# fpga-ground.net
KiCad netlist of a schematic drawn in Altium Designer
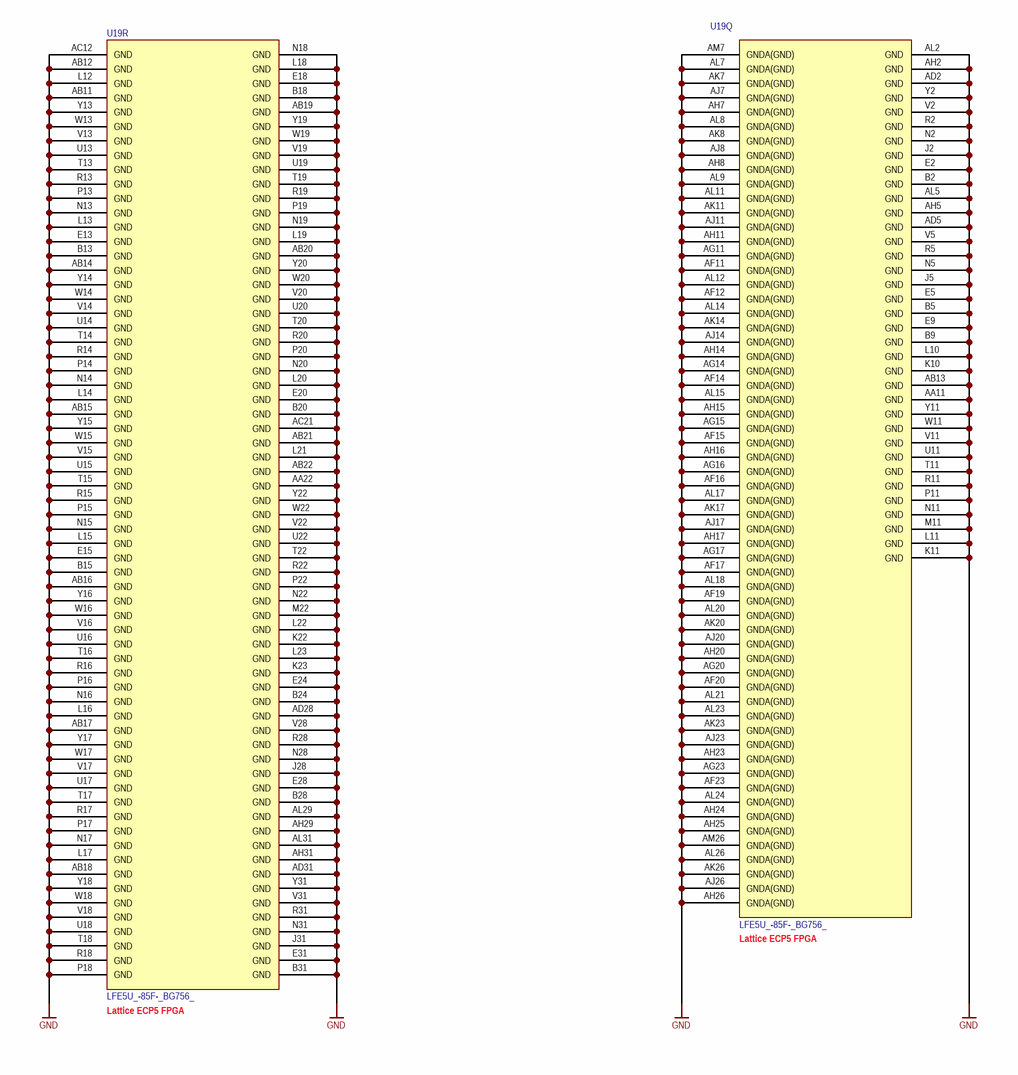
[diagram p0: fpga-ground.SchDoc]

(export (version "E")
  (design (tool "Eeschema 10.0.6"))
  (components
    (comp (ref "U19")
      (value "LFE5U_-85F-_BG756_")
      (footprint "lattice:caBGA756")
      (description "ECP5 FPGA, 85k LUT, 756-caBGA")
      (fields (field (name "MANUFACTURER") "Lattice Semiconductor"))
      (libsource (lib "lattice") (part "LFE5U_-85F-_BG756_"))
    )
  )
  (nets
    (net (code "1") (name "GND") (class "Default")
      (node (ref "U19") (pin "AA11") (pinfunction "GND_AA11") (pintype "power_in"))
      (node (ref "U19") (pin "AA22") (pinfunction "GND_AA22") (pintype "power_in"))
      (node (ref "U19") (pin "AB11") (pinfunction "GND_AB11") (pintype "power_in"))
      (node (ref "U19") (pin "AB12") (pinfunction "GND_AB12") (pintype "power_in"))
      (node (ref "U19") (pin "AB13") (pinfunction "GND_AB13") (pintype "power_in"))
      (node (ref "U19") (pin "AB14") (pinfunction "GND_AB14") (pintype "power_in"))
      (node (ref "U19") (pin "AB15") (pinfunction "GND_AB15") (pintype "power_in"))
      (node (ref "U19") (pin "AB16") (pinfunction "GND_AB16") (pintype "power_in"))
      (node (ref "U19") (pin "AB17") (pinfunction "GND_AB17") (pintype "power_in"))
      (node (ref "U19") (pin "AB18") (pinfunction "GND_AB18") (pintype "power_in"))
      (node (ref "U19") (pin "AB19") (pinfunction "GND_AB19") (pintype "power_in"))
      (node (ref "U19") (pin "AB20") (pinfunction "GND_AB20") (pintype "power_in"))
      (node (ref "U19") (pin "AB21") (pinfunction "GND_AB21") (pintype "power_in"))
      (node (ref "U19") (pin "AB22") (pinfunction "GND_AB22") (pintype "power_in"))
      (node (ref "U19") (pin "AC12") (pinfunction "GND_AC12") (pintype "power_in"))
      (node (ref "U19") (pin "AC21") (pinfunction "GND_AC21") (pintype "power_in"))
      (node (ref "U19") (pin "AD2") (pinfunction "GND_AD2") (pintype "power_in"))
      (node (ref "U19") (pin "AD28") (pinfunction "GND_AD28") (pintype "power_in"))
      (node (ref "U19") (pin "AD31") (pinfunction "GND_AD31") (pintype "power_in"))
      (node (ref "U19") (pin "AD5") (pinfunction "GND_AD5") (pintype "power_in"))
      (node (ref "U19") (pin "AF11") (pinfunction "GNDA(GND)_AF11") (pintype "power_in"))
      (node (ref "U19") (pin "AF12") (pinfunction "GNDA(GND)_AF12") (pintype "power_in"))
      (node (ref "U19") (pin "AF14") (pinfunction "GNDA(GND)_AF14") (pintype "power_in"))
      (node (ref "U19") (pin "AF15") (pinfunction "GNDA(GND)_AF15") (pintype "power_in"))
      (node (ref "U19") (pin "AF16") (pinfunction "GNDA(GND)_AF16") (pintype "power_in"))
      (node (ref "U19") (pin "AF17") (pinfunction "GNDA(GND)_AF17") (pintype "power_in"))
      (node (ref "U19") (pin "AF19") (pinfunction "GNDA(GND)_AF19") (pintype "power_in"))
      (node (ref "U19") (pin "AF20") (pinfunction "GNDA(GND)_AF20") (pintype "power_in"))
      (node (ref "U19") (pin "AF23") (pinfunction "GNDA(GND)_AF23") (pintype "power_in"))
      (node (ref "U19") (pin "AG11") (pinfunction "GNDA(GND)_AG11") (pintype "power_in"))
      (node (ref "U19") (pin "AG14") (pinfunction "GNDA(GND)_AG14") (pintype "power_in"))
      (node (ref "U19") (pin "AG15") (pinfunction "GNDA(GND)_AG15") (pintype "power_in"))
      (node (ref "U19") (pin "AG16") (pinfunction "GNDA(GND)_AG16") (pintype "power_in"))
      (node (ref "U19") (pin "AG17") (pinfunction "GNDA(GND)_AG17") (pintype "power_in"))
      (node (ref "U19") (pin "AG20") (pinfunction "GNDA(GND)_AG20") (pintype "power_in"))
      (node (ref "U19") (pin "AG23") (pinfunction "GNDA(GND)_AG23") (pintype "power_in"))
      (node (ref "U19") (pin "AH11") (pinfunction "GNDA(GND)_AH11") (pintype "power_in"))
      (node (ref "U19") (pin "AH14") (pinfunction "GNDA(GND)_AH14") (pintype "power_in"))
      (node (ref "U19") (pin "AH15") (pinfunction "GNDA(GND)_AH15") (pintype "power_in"))
      (node (ref "U19") (pin "AH16") (pinfunction "GNDA(GND)_AH16") (pintype "power_in"))
      (node (ref "U19") (pin "AH17") (pinfunction "GNDA(GND)_AH17") (pintype "power_in"))
      (node (ref "U19") (pin "AH2") (pinfunction "GND_AH2") (pintype "power_in"))
      (node (ref "U19") (pin "AH20") (pinfunction "GNDA(GND)_AH20") (pintype "power_in"))
      (node (ref "U19") (pin "AH23") (pinfunction "GNDA(GND)_AH23") (pintype "power_in"))
      (node (ref "U19") (pin "AH24") (pinfunction "GNDA(GND)_AH24") (pintype "power_in"))
      (node (ref "U19") (pin "AH25") (pinfunction "GNDA(GND)_AH25") (pintype "power_in"))
      (node (ref "U19") (pin "AH26") (pinfunction "GNDA(GND)_AH26") (pintype "power_in"))
      (node (ref "U19") (pin "AH29") (pinfunction "GND_AH29") (pintype "power_in"))
      (node (ref "U19") (pin "AH31") (pinfunction "GND_AH31") (pintype "power_in"))
      (node (ref "U19") (pin "AH5") (pinfunction "GND_AH5") (pintype "power_in"))
      (node (ref "U19") (pin "AH7") (pinfunction "GNDA(GND)_AH7") (pintype "power_in"))
      (node (ref "U19") (pin "AH8") (pinfunction "GNDA(GND)_AH8") (pintype "power_in"))
      (node (ref "U19") (pin "AJ11") (pinfunction "GNDA(GND)_AJ11") (pintype "power_in"))
      (node (ref "U19") (pin "AJ14") (pinfunction "GNDA(GND)_AJ14") (pintype "power_in"))
      (node (ref "U19") (pin "AJ17") (pinfunction "GNDA(GND)_AJ17") (pintype "power_in"))
      (node (ref "U19") (pin "AJ20") (pinfunction "GNDA(GND)_AJ20") (pintype "power_in"))
      (node (ref "U19") (pin "AJ23") (pinfunction "GNDA(GND)_AJ23") (pintype "power_in"))
      (node (ref "U19") (pin "AJ26") (pinfunction "GNDA(GND)_AJ26") (pintype "power_in"))
      (node (ref "U19") (pin "AJ7") (pinfunction "GNDA(GND)_AJ7") (pintype "power_in"))
      (node (ref "U19") (pin "AJ8") (pinfunction "GNDA(GND)_AJ8") (pintype "power_in"))
      (node (ref "U19") (pin "AK11") (pinfunction "GNDA(GND)_AK11") (pintype "power_in"))
      (node (ref "U19") (pin "AK14") (pinfunction "GNDA(GND)_AK14") (pintype "power_in"))
      (node (ref "U19") (pin "AK17") (pinfunction "GNDA(GND)_AK17") (pintype "power_in"))
      (node (ref "U19") (pin "AK20") (pinfunction "GNDA(GND)_AK20") (pintype "power_in"))
      (node (ref "U19") (pin "AK23") (pinfunction "GNDA(GND)_AK23") (pintype "power_in"))
      (node (ref "U19") (pin "AK26") (pinfunction "GNDA(GND)_AK26") (pintype "power_in"))
      (node (ref "U19") (pin "AK7") (pinfunction "GNDA(GND)_AK7") (pintype "power_in"))
      (node (ref "U19") (pin "AK8") (pinfunction "GNDA(GND)_AK8") (pintype "power_in"))
      (node (ref "U19") (pin "AL11") (pinfunction "GNDA(GND)_AL11") (pintype "power_in"))
      (node (ref "U19") (pin "AL12") (pinfunction "GNDA(GND)_AL12") (pintype "power_in"))
      (node (ref "U19") (pin "AL14") (pinfunction "GNDA(GND)_AL14") (pintype "power_in"))
      (node (ref "U19") (pin "AL15") (pinfunction "GNDA(GND)_AL15") (pintype "power_in"))
      (node (ref "U19") (pin "AL17") (pinfunction "GNDA(GND)_AL17") (pintype "power_in"))
      (node (ref "U19") (pin "AL18") (pinfunction "GNDA(GND)_AL18") (pintype "power_in"))
      (node (ref "U19") (pin "AL2") (pinfunction "GND_AL2") (pintype "power_in"))
      (node (ref "U19") (pin "AL20") (pinfunction "GNDA(GND)_AL20") (pintype "power_in"))
      (node (ref "U19") (pin "AL21") (pinfunction "GNDA(GND)_AL21") (pintype "power_in"))
      (node (ref "U19") (pin "AL23") (pinfunction "GNDA(GND)_AL23") (pintype "power_in"))
      (node (ref "U19") (pin "AL24") (pinfunction "GNDA(GND)_AL24") (pintype "power_in"))
      (node (ref "U19") (pin "AL26") (pinfunction "GNDA(GND)_AL26") (pintype "power_in"))
      (node (ref "U19") (pin "AL29") (pinfunction "GND_AL29") (pintype "power_in"))
      (node (ref "U19") (pin "AL31") (pinfunction "GND_AL31") (pintype "power_in"))
      (node (ref "U19") (pin "AL5") (pinfunction "GND_AL5") (pintype "power_in"))
      (node (ref "U19") (pin "AL7") (pinfunction "GNDA(GND)_AL7") (pintype "power_in"))
      (node (ref "U19") (pin "AL8") (pinfunction "GNDA(GND)_AL8") (pintype "power_in"))
      (node (ref "U19") (pin "AL9") (pinfunction "GNDA(GND)_AL9") (pintype "power_in"))
      (node (ref "U19") (pin "AM26") (pinfunction "GNDA(GND)_AM26") (pintype "power_in"))
      (node (ref "U19") (pin "AM7") (pinfunction "GNDA(GND)_AM7") (pintype "power_in"))
      (node (ref "U19") (pin "B13") (pinfunction "GND_B13") (pintype "power_in"))
      (node (ref "U19") (pin "B15") (pinfunction "GND_B15") (pintype "power_in"))
      (node (ref "U19") (pin "B18") (pinfunction "GND_B18") (pintype "power_in"))
      (node (ref "U19") (pin "B2") (pinfunction "GND_B2") (pintype "power_in"))
      (node (ref "U19") (pin "B20") (pinfunction "GND_B20") (pintype "power_in"))
      (node (ref "U19") (pin "B24") (pinfunction "GND_B24") (pintype "power_in"))
      (node (ref "U19") (pin "B28") (pinfunction "GND_B28") (pintype "power_in"))
      (node (ref "U19") (pin "B31") (pinfunction "GND_B31") (pintype "power_in"))
      (node (ref "U19") (pin "B5") (pinfunction "GND_B5") (pintype "power_in"))
      (node (ref "U19") (pin "B9") (pinfunction "GND_B9") (pintype "power_in"))
      (node (ref "U19") (pin "E13") (pinfunction "GND_E13") (pintype "power_in"))
      (node (ref "U19") (pin "E15") (pinfunction "GND_E15") (pintype "power_in"))
      (node (ref "U19") (pin "E18") (pinfunction "GND_E18") (pintype "power_in"))
      (node (ref "U19") (pin "E2") (pinfunction "GND_E2") (pintype "power_in"))
      (node (ref "U19") (pin "E20") (pinfunction "GND_E20") (pintype "power_in"))
      (node (ref "U19") (pin "E24") (pinfunction "GND_E24") (pintype "power_in"))
      (node (ref "U19") (pin "E28") (pinfunction "GND_E28") (pintype "power_in"))
      (node (ref "U19") (pin "E31") (pinfunction "GND_E31") (pintype "power_in"))
      (node (ref "U19") (pin "E5") (pinfunction "GND_E5") (pintype "power_in"))
      (node (ref "U19") (pin "E9") (pinfunction "GND_E9") (pintype "power_in"))
      (node (ref "U19") (pin "J2") (pinfunction "GND_J2") (pintype "power_in"))
      (node (ref "U19") (pin "J28") (pinfunction "GND_J28") (pintype "power_in"))
      (node (ref "U19") (pin "J31") (pinfunction "GND_J31") (pintype "power_in"))
      (node (ref "U19") (pin "J5") (pinfunction "GND_J5") (pintype "power_in"))
      (node (ref "U19") (pin "K10") (pinfunction "GND_K10") (pintype "power_in"))
      (node (ref "U19") (pin "K11") (pinfunction "GND_K11") (pintype "power_in"))
      (node (ref "U19") (pin "K22") (pinfunction "GND_K22") (pintype "power_in"))
      (node (ref "U19") (pin "K23") (pinfunction "GND_K23") (pintype "power_in"))
      (node (ref "U19") (pin "L10") (pinfunction "GND_L10") (pintype "power_in"))
      (node (ref "U19") (pin "L11") (pinfunction "GND_L11") (pintype "power_in"))
      (node (ref "U19") (pin "L12") (pinfunction "GND_L12") (pintype "power_in"))
      (node (ref "U19") (pin "L13") (pinfunction "GND_L13") (pintype "power_in"))
      (node (ref "U19") (pin "L14") (pinfunction "GND_L14") (pintype "power_in"))
      (node (ref "U19") (pin "L15") (pinfunction "GND_L15") (pintype "power_in"))
      (node (ref "U19") (pin "L16") (pinfunction "GND_L16") (pintype "power_in"))
      (node (ref "U19") (pin "L17") (pinfunction "GND_L17") (pintype "power_in"))
      (node (ref "U19") (pin "L18") (pinfunction "GND_L18") (pintype "power_in"))
      (node (ref "U19") (pin "L19") (pinfunction "GND_L19") (pintype "power_in"))
      (node (ref "U19") (pin "L20") (pinfunction "GND_L20") (pintype "power_in"))
      (node (ref "U19") (pin "L21") (pinfunction "GND_L21") (pintype "power_in"))
      (node (ref "U19") (pin "L22") (pinfunction "GND_L22") (pintype "power_in"))
      (node (ref "U19") (pin "L23") (pinfunction "GND_L23") (pintype "power_in"))
      (node (ref "U19") (pin "M11") (pinfunction "GND_M11") (pintype "power_in"))
      (node (ref "U19") (pin "M22") (pinfunction "GND_M22") (pintype "power_in"))
      (node (ref "U19") (pin "N11") (pinfunction "GND_N11") (pintype "power_in"))
      (node (ref "U19") (pin "N13") (pinfunction "GND_N13") (pintype "power_in"))
      (node (ref "U19") (pin "N14") (pinfunction "GND_N14") (pintype "power_in"))
      (node (ref "U19") (pin "N15") (pinfunction "GND_N15") (pintype "power_in"))
      (node (ref "U19") (pin "N16") (pinfunction "GND_N16") (pintype "power_in"))
      (node (ref "U19") (pin "N17") (pinfunction "GND_N17") (pintype "power_in"))
      (node (ref "U19") (pin "N18") (pinfunction "GND_N18") (pintype "power_in"))
      (node (ref "U19") (pin "N19") (pinfunction "GND_N19") (pintype "power_in"))
      (node (ref "U19") (pin "N2") (pinfunction "GND_N2") (pintype "power_in"))
      (node (ref "U19") (pin "N20") (pinfunction "GND_N20") (pintype "power_in"))
      (node (ref "U19") (pin "N22") (pinfunction "GND_N22") (pintype "power_in"))
      (node (ref "U19") (pin "N28") (pinfunction "GND_N28") (pintype "power_in"))
      (node (ref "U19") (pin "N31") (pinfunction "GND_N31") (pintype "power_in"))
      (node (ref "U19") (pin "N5") (pinfunction "GND_N5") (pintype "power_in"))
      (node (ref "U19") (pin "P11") (pinfunction "GND_P11") (pintype "power_in"))
      (node (ref "U19") (pin "P13") (pinfunction "GND_P13") (pintype "power_in"))
      (node (ref "U19") (pin "P14") (pinfunction "GND_P14") (pintype "power_in"))
      (node (ref "U19") (pin "P15") (pinfunction "GND_P15") (pintype "power_in"))
      (node (ref "U19") (pin "P16") (pinfunction "GND_P16") (pintype "power_in"))
      (node (ref "U19") (pin "P17") (pinfunction "GND_P17") (pintype "power_in"))
      (node (ref "U19") (pin "P18") (pinfunction "GND_P18") (pintype "power_in"))
      (node (ref "U19") (pin "P19") (pinfunction "GND_P19") (pintype "power_in"))
      (node (ref "U19") (pin "P20") (pinfunction "GND_P20") (pintype "power_in"))
      (node (ref "U19") (pin "P22") (pinfunction "GND_P22") (pintype "power_in"))
      (node (ref "U19") (pin "R11") (pinfunction "GND_R11") (pintype "power_in"))
      (node (ref "U19") (pin "R13") (pinfunction "GND_R13") (pintype "power_in"))
      (node (ref "U19") (pin "R14") (pinfunction "GND_R14") (pintype "power_in"))
      (node (ref "U19") (pin "R15") (pinfunction "GND_R15") (pintype "power_in"))
      (node (ref "U19") (pin "R16") (pinfunction "GND_R16") (pintype "power_in"))
      (node (ref "U19") (pin "R17") (pinfunction "GND_R17") (pintype "power_in"))
      (node (ref "U19") (pin "R18") (pinfunction "GND_R18") (pintype "power_in"))
      (node (ref "U19") (pin "R19") (pinfunction "GND_R19") (pintype "power_in"))
      (node (ref "U19") (pin "R2") (pinfunction "GND_R2") (pintype "power_in"))
      (node (ref "U19") (pin "R20") (pinfunction "GND_R20") (pintype "power_in"))
      (node (ref "U19") (pin "R22") (pinfunction "GND_R22") (pintype "power_in"))
      (node (ref "U19") (pin "R28") (pinfunction "GND_R28") (pintype "power_in"))
      (node (ref "U19") (pin "R31") (pinfunction "GND_R31") (pintype "power_in"))
      (node (ref "U19") (pin "R5") (pinfunction "GND_R5") (pintype "power_in"))
      (node (ref "U19") (pin "T11") (pinfunction "GND_T11") (pintype "power_in"))
      (node (ref "U19") (pin "T13") (pinfunction "GND_T13") (pintype "power_in"))
      (node (ref "U19") (pin "T14") (pinfunction "GND_T14") (pintype "power_in"))
      (node (ref "U19") (pin "T15") (pinfunction "GND_T15") (pintype "power_in"))
      (node (ref "U19") (pin "T16") (pinfunction "GND_T16") (pintype "power_in"))
      (node (ref "U19") (pin "T17") (pinfunction "GND_T17") (pintype "power_in"))
      (node (ref "U19") (pin "T18") (pinfunction "GND_T18") (pintype "power_in"))
      (node (ref "U19") (pin "T19") (pinfunction "GND_T19") (pintype "power_in"))
      (node (ref "U19") (pin "T20") (pinfunction "GND_T20") (pintype "power_in"))
      (node (ref "U19") (pin "T22") (pinfunction "GND_T22") (pintype "power_in"))
      (node (ref "U19") (pin "U11") (pinfunction "GND_U11") (pintype "power_in"))
      (node (ref "U19") (pin "U13") (pinfunction "GND_U13") (pintype "power_in"))
      (node (ref "U19") (pin "U14") (pinfunction "GND_U14") (pintype "power_in"))
      (node (ref "U19") (pin "U15") (pinfunction "GND_U15") (pintype "power_in"))
      (node (ref "U19") (pin "U16") (pinfunction "GND_U16") (pintype "power_in"))
      (node (ref "U19") (pin "U17") (pinfunction "GND_U17") (pintype "power_in"))
      (node (ref "U19") (pin "U18") (pinfunction "GND_U18") (pintype "power_in"))
      (node (ref "U19") (pin "U19") (pinfunction "GND_U19") (pintype "power_in"))
      (node (ref "U19") (pin "U20") (pinfunction "GND_U20") (pintype "power_in"))
      (node (ref "U19") (pin "U22") (pinfunction "GND_U22") (pintype "power_in"))
      (node (ref "U19") (pin "V11") (pinfunction "GND_V11") (pintype "power_in"))
      (node (ref "U19") (pin "V13") (pinfunction "GND_V13") (pintype "power_in"))
      (node (ref "U19") (pin "V14") (pinfunction "GND_V14") (pintype "power_in"))
      (node (ref "U19") (pin "V15") (pinfunction "GND_V15") (pintype "power_in"))
      (node (ref "U19") (pin "V16") (pinfunction "GND_V16") (pintype "power_in"))
      (node (ref "U19") (pin "V17") (pinfunction "GND_V17") (pintype "power_in"))
      (node (ref "U19") (pin "V18") (pinfunction "GND_V18") (pintype "power_in"))
      (node (ref "U19") (pin "V19") (pinfunction "GND_V19") (pintype "power_in"))
      (node (ref "U19") (pin "V2") (pinfunction "GND_V2") (pintype "power_in"))
      (node (ref "U19") (pin "V20") (pinfunction "GND_V20") (pintype "power_in"))
      (node (ref "U19") (pin "V22") (pinfunction "GND_V22") (pintype "power_in"))
      (node (ref "U19") (pin "V28") (pinfunction "GND_V28") (pintype "power_in"))
      (node (ref "U19") (pin "V31") (pinfunction "GND_V31") (pintype "power_in"))
      (node (ref "U19") (pin "V5") (pinfunction "GND_V5") (pintype "power_in"))
      (node (ref "U19") (pin "W11") (pinfunction "GND_W11") (pintype "power_in"))
      (node (ref "U19") (pin "W13") (pinfunction "GND_W13") (pintype "power_in"))
      (node (ref "U19") (pin "W14") (pinfunction "GND_W14") (pintype "power_in"))
      (node (ref "U19") (pin "W15") (pinfunction "GND_W15") (pintype "power_in"))
      (node (ref "U19") (pin "W16") (pinfunction "GND_W16") (pintype "power_in"))
      (node (ref "U19") (pin "W17") (pinfunction "GND_W17") (pintype "power_in"))
      (node (ref "U19") (pin "W18") (pinfunction "GND_W18") (pintype "power_in"))
      (node (ref "U19") (pin "W19") (pinfunction "GND_W19") (pintype "power_in"))
      (node (ref "U19") (pin "W20") (pinfunction "GND_W20") (pintype "power_in"))
      (node (ref "U19") (pin "W22") (pinfunction "GND_W22") (pintype "power_in"))
      (node (ref "U19") (pin "Y11") (pinfunction "GND_Y11") (pintype "power_in"))
      (node (ref "U19") (pin "Y13") (pinfunction "GND_Y13") (pintype "power_in"))
      (node (ref "U19") (pin "Y14") (pinfunction "GND_Y14") (pintype "power_in"))
      (node (ref "U19") (pin "Y15") (pinfunction "GND_Y15") (pintype "power_in"))
      (node (ref "U19") (pin "Y16") (pinfunction "GND_Y16") (pintype "power_in"))
      (node (ref "U19") (pin "Y17") (pinfunction "GND_Y17") (pintype "power_in"))
      (node (ref "U19") (pin "Y18") (pinfunction "GND_Y18") (pintype "power_in"))
      (node (ref "U19") (pin "Y19") (pinfunction "GND_Y19") (pintype "power_in"))
      (node (ref "U19") (pin "Y2") (pinfunction "GND_Y2") (pintype "power_in"))
      (node (ref "U19") (pin "Y20") (pinfunction "GND_Y20") (pintype "power_in"))
      (node (ref "U19") (pin "Y22") (pinfunction "GND_Y22") (pintype "power_in"))
      (node (ref "U19") (pin "Y31") (pinfunction "GND_Y31") (pintype "power_in"))
    )
  )
)
